# nbiot_gps.net
KiCad netlist of a schematic drawn in Altium Designer
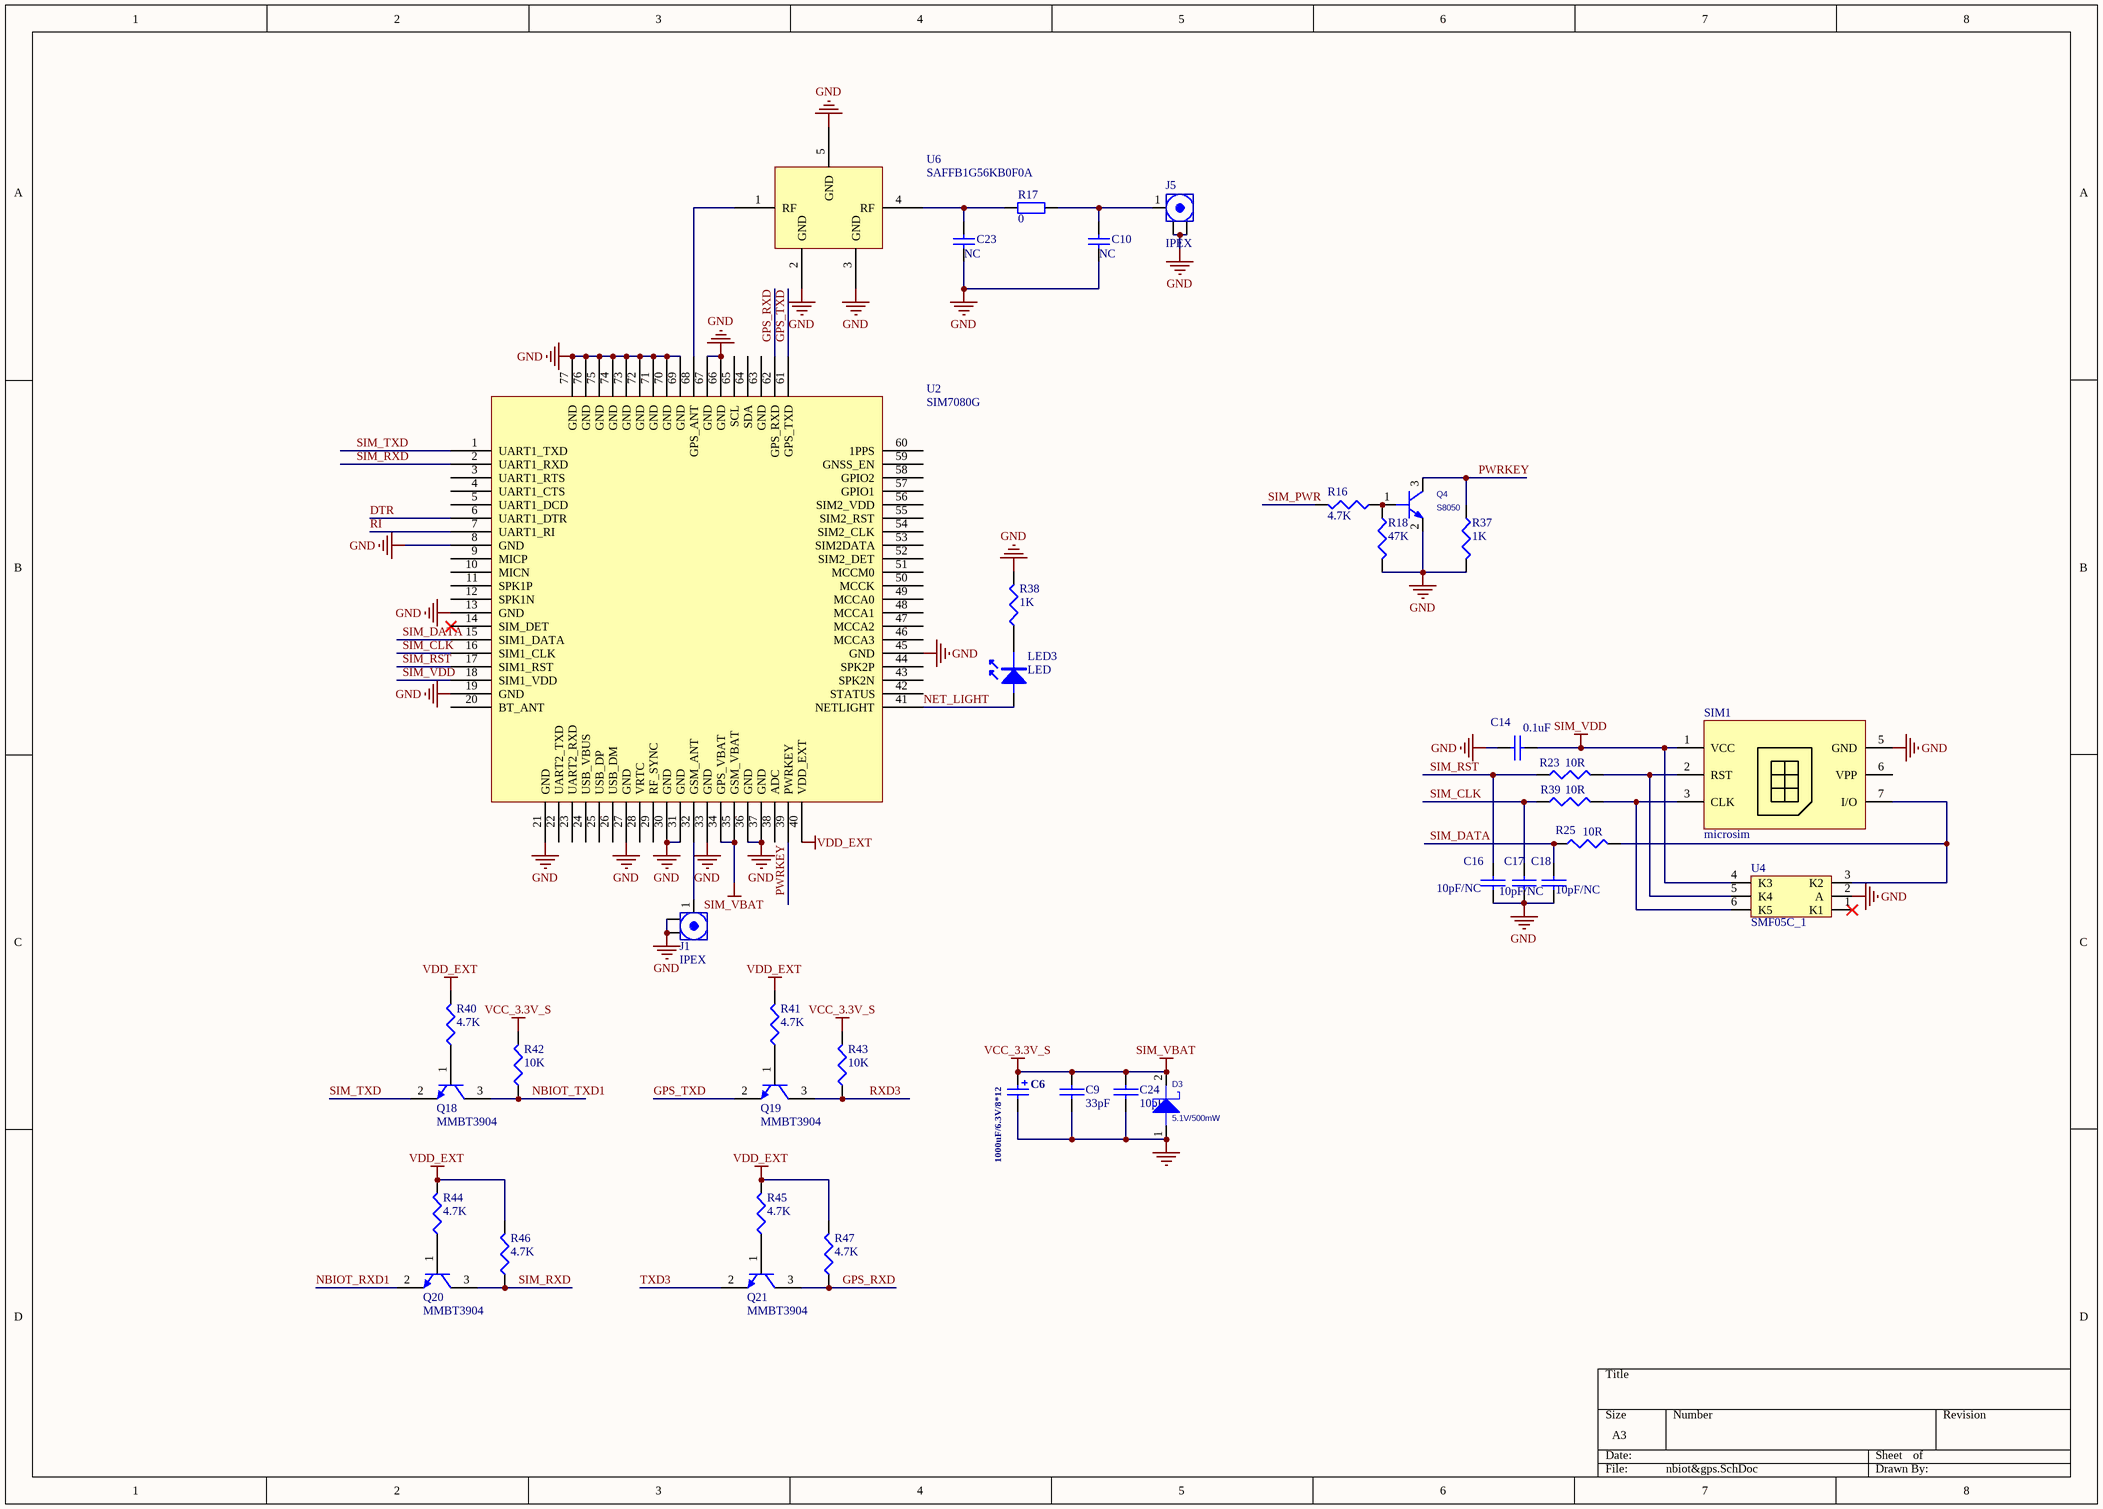
[diagram p0: nbiot&gps.SchDoc]

(export (version "E")
  (design (tool "Eeschema 10.0.6"))
  (components
    (comp (ref "C6")
      (value "1000uF/6.3V/8*12")
      (footprint "8*12")
      (description "Polarized Capacitor (Surface Mount)")
      (libsource (lib "KT_iBeacon") (part "Cap Pol3"))
    )
    (comp (ref "C9")
      (value "33pF")
      (footprint "0603C")
      (description "Capacitor")
      (libsource (lib "ZWLIntegrated_Library") (part "CAP"))
    )
    (comp (ref "C10")
      (value "NC")
      (footprint "0603C")
      (description "Capacitor")
      (fields (field (name "PUBLISHER") "Altium Limited"))
      (libsource (lib "Miscellaneous Devices") (part "Cap"))
    )
    (comp (ref "C14")
      (value "0.1uF")
      (footprint "0603C")
      (description "Capacitor")
      (libsource (lib "ZWLIntegrated_Library") (part "CAP"))
    )
    (comp (ref "C16")
      (value "10pF/NC")
      (footprint "0603C")
      (description "Capacitor")
      (libsource (lib "ZWLIntegrated_Library") (part "CAP"))
    )
    (comp (ref "C17")
      (value "10pF/NC")
      (footprint "0603C")
      (description "Capacitor")
      (libsource (lib "ZWLIntegrated_Library") (part "CAP"))
    )
    (comp (ref "C18")
      (value "10pF/NC")
      (footprint "0603C")
      (description "Capacitor")
      (libsource (lib "ZWLIntegrated_Library") (part "CAP"))
    )
    (comp (ref "C23")
      (value "NC")
      (footprint "0603C")
      (description "Capacitor")
      (fields (field (name "PUBLISHER") "Altium Limited"))
      (libsource (lib "Miscellaneous Devices") (part "Cap"))
    )
    (comp (ref "C24")
      (value "10pF")
      (footprint "0603C")
      (description "Capacitor")
      (libsource (lib "ZWLIntegrated_Library") (part "CAP"))
    )
    (comp (ref "D3")
      (value "5.1V/500mW")
      (footprint "LL-34(D1206)")
      (fields (field (name "Comment") "DIODE_SCHOTTKY_0"))
      (libsource (lib "KT_iBeacon") (part "DIODE_SCHOTTKY_0"))
    )
    (comp (ref "J1") (value "IPEX") (footprint "RF-UFL") (libsource (lib "我的元件库") (part "ANT")))
    (comp (ref "J5") (value "IPEX") (footprint "RF-UFL") (libsource (lib "我的元件库") (part "ANT")))
    (comp (ref "LED3") (value "LED") (footprint "0603LED") (libsource (lib "我的元件库") (part "LED")))
    (comp (ref "Q4") (value "S8050") (footprint "SOT23") (libsource (lib "*") (part "2N1069_1")))
    (comp (ref "Q18") (value "MMBT3904") (footprint "SOT23-3") (libsource (lib "Schlib1") (part "NPN")))
    (comp (ref "Q19") (value "MMBT3904") (footprint "SOT23-3") (libsource (lib "Schlib1") (part "NPN")))
    (comp (ref "Q20") (value "MMBT3904") (footprint "SOT23-3") (libsource (lib "Schlib1") (part "NPN")))
    (comp (ref "Q21") (value "MMBT3904") (footprint "SOT23-3") (libsource (lib "Schlib1") (part "NPN")))
    (comp (ref "R16")
      (value "4.7K")
      (footprint "0603R")
      (libsource (lib "ZWLIntegrated_Library") (part "RES1"))
    )
    (comp (ref "R17")
      (value "0")
      (footprint "0603R")
      (description "Resistor")
      (fields (field (name "PUBLISHER") "Altium Limited"))
      (libsource (lib "Miscellaneous Devices") (part "Res2"))
    )
    (comp (ref "R18")
      (value "47K")
      (footprint "0603R")
      (libsource (lib "ZWLIntegrated_Library") (part "RES1"))
    )
    (comp (ref "R23")
      (value "10R")
      (footprint "0603R")
      (libsource (lib "ZWLIntegrated_Library") (part "RES1"))
    )
    (comp (ref "R25")
      (value "10R")
      (footprint "0603R")
      (libsource (lib "ZWLIntegrated_Library") (part "RES1"))
    )
    (comp (ref "R37")
      (value "1K")
      (footprint "0603R")
      (libsource (lib "ZWLIntegrated_Library") (part "RES1"))
    )
    (comp (ref "R38")
      (value "1K")
      (footprint "0603R")
      (libsource (lib "ZWLIntegrated_Library") (part "RES1"))
    )
    (comp (ref "R39")
      (value "10R")
      (footprint "0603R")
      (libsource (lib "ZWLIntegrated_Library") (part "RES1"))
    )
    (comp (ref "R40")
      (value "4.7K")
      (footprint "0603R")
      (libsource (lib "ZWLIntegrated_Library") (part "RES1"))
    )
    (comp (ref "R41")
      (value "4.7K")
      (footprint "0603R")
      (libsource (lib "ZWLIntegrated_Library") (part "RES1"))
    )
    (comp (ref "R42")
      (value "10K")
      (footprint "0603R")
      (libsource (lib "ZWLIntegrated_Library") (part "RES1"))
    )
    (comp (ref "R43")
      (value "10K")
      (footprint "0603R")
      (libsource (lib "ZWLIntegrated_Library") (part "RES1"))
    )
    (comp (ref "R44")
      (value "4.7K")
      (footprint "0603R")
      (libsource (lib "ZWLIntegrated_Library") (part "RES1"))
    )
    (comp (ref "R45")
      (value "4.7K")
      (footprint "0603R")
      (libsource (lib "ZWLIntegrated_Library") (part "RES1"))
    )
    (comp (ref "R46")
      (value "4.7K")
      (footprint "0603R")
      (libsource (lib "ZWLIntegrated_Library") (part "RES1"))
    )
    (comp (ref "R47")
      (value "4.7K")
      (footprint "0603R")
      (libsource (lib "ZWLIntegrated_Library") (part "RES1"))
    )
    (comp (ref "SIM1")
      (value "microsim")
      (footprint "Nano SIM")
      (libsource (lib "SIM800C 原理图库") (part "microsim"))
    )
    (comp (ref "U2")
      (value "SIM7080G")
      (footprint "SIM868")
      (libsource (lib "stm32") (part "SIM868E/SIM868"))
    )
    (comp (ref "U4")
      (value "SMF05C_1")
      (footprint "SC70-6L")
      (description "TVS")
      (libsource (lib "SIM800C 原理图库") (part "SMF05C_1"))
    )
    (comp (ref "U6")
      (value "SAFFB1G56KB0F0A")
      (footprint "SAFFB1G56KB0F0A")
      (libsource (lib "stm32") (part "SAFFB1G56KBOFA"))
    )
  )
  (nets
    (net (code "1") (name "/DTR") (class "Default")
      (node (ref "U2") (pin "6") (pinfunction "UART1_DTR_6") (pintype "passive"))
    )
    (net (code "2") (name "/GPS_RXD") (class "Default")
      (node (ref "Q21") (pin "3") (pinfunction "C_3") (pintype "passive"))
      (node (ref "R47") (pin "1") (pinfunction "1_1") (pintype "passive"))
      (node (ref "U2") (pin "62") (pinfunction "GPS_RXD_62") (pintype "passive"))
    )
    (net (code "3") (name "/GPS_TXD") (class "Default")
      (node (ref "Q19") (pin "2") (pinfunction "E_2") (pintype "passive"))
      (node (ref "U2") (pin "61") (pinfunction "GPS_TXD_61") (pintype "passive"))
    )
    (net (code "4") (name "/NBIOT_RXD1") (class "Default")
      (node (ref "Q20") (pin "2") (pinfunction "E_2") (pintype "passive"))
    )
    (net (code "5") (name "/NBIOT_TXD1") (class "Default")
      (node (ref "Q18") (pin "3") (pinfunction "C_3") (pintype "passive"))
      (node (ref "R42") (pin "1") (pinfunction "1_1") (pintype "passive"))
    )
    (net (code "6") (name "/NET_LIGHT") (class "Default")
      (node (ref "LED3") (pin "1") (pinfunction "1_1") (pintype "passive"))
      (node (ref "U2") (pin "41") (pinfunction "NETLIGHT_41") (pintype "passive"))
    )
    (net (code "7") (name "/PWRKEY") (class "Default")
      (node (ref "Q4") (pin "3") (pinfunction "C_3") (pintype "passive"))
      (node (ref "R37") (pin "1") (pinfunction "1_1") (pintype "passive"))
      (node (ref "U2") (pin "39") (pinfunction "PWRKEY_39") (pintype "passive"))
    )
    (net (code "8") (name "/RI") (class "Default")
      (node (ref "U2") (pin "7") (pinfunction "UART1_RI_7") (pintype "passive"))
    )
    (net (code "9") (name "/RXD3") (class "Default")
      (node (ref "Q19") (pin "3") (pinfunction "C_3") (pintype "passive"))
      (node (ref "R43") (pin "1") (pinfunction "1_1") (pintype "passive"))
    )
    (net (code "10") (name "/SIM_CLK") (class "Default")
      (node (ref "C17") (pin "2") (pinfunction "2_2") (pintype "passive"))
      (node (ref "R39") (pin "1") (pinfunction "1_1") (pintype "passive"))
      (node (ref "U2") (pin "16") (pinfunction "SIM1_CLK_16") (pintype "passive"))
    )
    (net (code "11") (name "/SIM_DATA") (class "Default")
      (node (ref "C18") (pin "2") (pinfunction "2_2") (pintype "passive"))
      (node (ref "R25") (pin "1") (pinfunction "1_1") (pintype "passive"))
      (node (ref "U2") (pin "15") (pinfunction "SIM1_DATA_15") (pintype "passive"))
    )
    (net (code "12") (name "/SIM_PWR") (class "Default")
      (node (ref "R16") (pin "2") (pinfunction "2_2") (pintype "passive"))
    )
    (net (code "13") (name "/SIM_RST") (class "Default")
      (node (ref "C16") (pin "2") (pinfunction "2_2") (pintype "passive"))
      (node (ref "R23") (pin "1") (pinfunction "1_1") (pintype "passive"))
      (node (ref "U2") (pin "17") (pinfunction "SIM1_RST_17") (pintype "passive"))
    )
    (net (code "14") (name "/SIM_RXD") (class "Default")
      (node (ref "Q20") (pin "3") (pinfunction "C_3") (pintype "passive"))
      (node (ref "R46") (pin "1") (pinfunction "1_1") (pintype "passive"))
      (node (ref "U2") (pin "2") (pinfunction "UART1_RXD_2") (pintype "passive"))
    )
    (net (code "15") (name "/SIM_TXD") (class "Default")
      (node (ref "Q18") (pin "2") (pinfunction "E_2") (pintype "passive"))
      (node (ref "U2") (pin "1") (pinfunction "UART1_TXD_1") (pintype "passive"))
    )
    (net (code "16") (name "/TXD3") (class "Default")
      (node (ref "Q21") (pin "2") (pinfunction "E_2") (pintype "passive"))
    )
    (net (code "17") (name "GND") (class "Default")
      (node (ref "C10") (pin "2") (pinfunction "2_2") (pintype "passive"))
      (node (ref "C14") (pin "1") (pinfunction "1_1") (pintype "passive"))
      (node (ref "C16") (pin "1") (pinfunction "1_1") (pintype "passive"))
      (node (ref "C17") (pin "1") (pinfunction "1_1") (pintype "passive"))
      (node (ref "C18") (pin "1") (pinfunction "1_1") (pintype "passive"))
      (node (ref "C23") (pin "2") (pinfunction "2_2") (pintype "passive"))
      (node (ref "C24") (pin "1") (pinfunction "1_1") (pintype "passive"))
      (node (ref "C6") (pin "2") (pinfunction "2_2") (pintype "passive"))
      (node (ref "C9") (pin "1") (pinfunction "1_1") (pintype "passive"))
      (node (ref "D3") (pin "1") (pinfunction "1_1") (pintype "passive"))
      (node (ref "J1") (pin "2") (pinfunction "Y_2") (pintype "passive"))
      (node (ref "J5") (pin "2") (pinfunction "Y_2") (pintype "passive"))
      (node (ref "Q4") (pin "2") (pinfunction "E_2") (pintype "passive"))
      (node (ref "R18") (pin "2") (pinfunction "2_2") (pintype "passive"))
      (node (ref "R37") (pin "2") (pinfunction "2_2") (pintype "passive"))
      (node (ref "R38") (pin "2") (pinfunction "2_2") (pintype "passive"))
      (node (ref "SIM1") (pin "5") (pinfunction "GND_5") (pintype "passive"))
      (node (ref "U2") (pin "13") (pinfunction "GND_13") (pintype "passive"))
      (node (ref "U2") (pin "19") (pinfunction "GND_19") (pintype "passive"))
      (node (ref "U2") (pin "21") (pinfunction "GND_21") (pintype "passive"))
      (node (ref "U2") (pin "27") (pinfunction "GND_27") (pintype "passive"))
      (node (ref "U2") (pin "30") (pinfunction "GND_30") (pintype "passive"))
      (node (ref "U2") (pin "31") (pinfunction "GND_31") (pintype "passive"))
      (node (ref "U2") (pin "33") (pinfunction "GND_33") (pintype "passive"))
      (node (ref "U2") (pin "36") (pinfunction "GND_36") (pintype "passive"))
      (node (ref "U2") (pin "37") (pinfunction "GND_37") (pintype "passive"))
      (node (ref "U2") (pin "45") (pinfunction "GND_45") (pintype "passive"))
      (node (ref "U2") (pin "66") (pinfunction "GND_66") (pintype "passive"))
      (node (ref "U2") (pin "67") (pinfunction "GND_67") (pintype "passive"))
      (node (ref "U2") (pin "69") (pinfunction "GND_69") (pintype "passive"))
      (node (ref "U2") (pin "70") (pinfunction "GND_70") (pintype "passive"))
      (node (ref "U2") (pin "71") (pinfunction "GND_71") (pintype "passive"))
      (node (ref "U2") (pin "72") (pinfunction "GND_72") (pintype "passive"))
      (node (ref "U2") (pin "73") (pinfunction "GND_73") (pintype "passive"))
      (node (ref "U2") (pin "74") (pinfunction "GND_74") (pintype "passive"))
      (node (ref "U2") (pin "75") (pinfunction "GND_75") (pintype "passive"))
      (node (ref "U2") (pin "76") (pinfunction "GND_76") (pintype "passive"))
      (node (ref "U2") (pin "77") (pinfunction "GND_77") (pintype "passive"))
      (node (ref "U2") (pin "8") (pinfunction "GND_8") (pintype "passive"))
      (node (ref "U4") (pin "2") (pinfunction "A_2") (pintype "passive"))
      (node (ref "U6") (pin "2") (pinfunction "GND_2") (pintype "passive"))
      (node (ref "U6") (pin "3") (pinfunction "GND_3") (pintype "passive"))
      (node (ref "U6") (pin "5") (pinfunction "GND_5") (pintype "passive"))
    )
    (net (code "18") (name "Net-(C23-Pad1)") (class "Default")
      (node (ref "C23") (pin "1") (pinfunction "1_1") (pintype "passive"))
      (node (ref "R17") (pin "1") (pinfunction "1_1") (pintype "passive"))
      (node (ref "U6") (pin "4") (pinfunction "RF_4") (pintype "passive"))
    )
    (net (code "19") (name "Net-(J1-X)") (class "Default")
      (node (ref "J1") (pin "1") (pinfunction "X_1") (pintype "passive"))
      (node (ref "U2") (pin "32") (pinfunction "GSM_ANT_32") (pintype "passive"))
    )
    (net (code "20") (name "Net-(J5-X)") (class "Default")
      (node (ref "C10") (pin "1") (pinfunction "1_1") (pintype "passive"))
      (node (ref "J5") (pin "1") (pinfunction "X_1") (pintype "passive"))
      (node (ref "R17") (pin "2") (pinfunction "2_2") (pintype "passive"))
    )
    (net (code "21") (name "Net-(LED3-Pad2)") (class "Default")
      (node (ref "LED3") (pin "2") (pinfunction "2_2") (pintype "passive"))
      (node (ref "R38") (pin "1") (pinfunction "1_1") (pintype "passive"))
    )
    (net (code "22") (name "Net-(Q4-B)") (class "Default")
      (node (ref "Q4") (pin "1") (pinfunction "B_1") (pintype "passive"))
      (node (ref "R16") (pin "1") (pinfunction "1_1") (pintype "passive"))
      (node (ref "R18") (pin "1") (pinfunction "1_1") (pintype "passive"))
    )
    (net (code "23") (name "Net-(Q18-B)") (class "Default")
      (node (ref "Q18") (pin "1") (pinfunction "B_1") (pintype "passive"))
      (node (ref "R40") (pin "1") (pinfunction "1_1") (pintype "passive"))
    )
    (net (code "24") (name "Net-(Q19-B)") (class "Default")
      (node (ref "Q19") (pin "1") (pinfunction "B_1") (pintype "passive"))
      (node (ref "R41") (pin "1") (pinfunction "1_1") (pintype "passive"))
    )
    (net (code "25") (name "Net-(Q20-B)") (class "Default")
      (node (ref "Q20") (pin "1") (pinfunction "B_1") (pintype "passive"))
      (node (ref "R44") (pin "1") (pinfunction "1_1") (pintype "passive"))
    )
    (net (code "26") (name "Net-(Q21-B)") (class "Default")
      (node (ref "Q21") (pin "1") (pinfunction "B_1") (pintype "passive"))
      (node (ref "R45") (pin "1") (pinfunction "1_1") (pintype "passive"))
    )
    (net (code "27") (name "Net-(SIM1-CLK)") (class "Default")
      (node (ref "R39") (pin "2") (pinfunction "2_2") (pintype "passive"))
      (node (ref "SIM1") (pin "3") (pinfunction "CLK_3") (pintype "passive"))
      (node (ref "U4") (pin "6") (pinfunction "K5_6") (pintype "passive"))
    )
    (net (code "28") (name "Net-(SIM1-I{slash}O)") (class "Default")
      (node (ref "R25") (pin "2") (pinfunction "2_2") (pintype "passive"))
      (node (ref "SIM1") (pin "7") (pinfunction "I/O_7") (pintype "passive"))
      (node (ref "U4") (pin "3") (pinfunction "K2_3") (pintype "passive"))
    )
    (net (code "29") (name "Net-(SIM1-RST)") (class "Default")
      (node (ref "R23") (pin "2") (pinfunction "2_2") (pintype "passive"))
      (node (ref "SIM1") (pin "2") (pinfunction "RST_2") (pintype "passive"))
      (node (ref "U4") (pin "5") (pinfunction "K4_5") (pintype "passive"))
    )
    (net (code "30") (name "Net-(U2-GPS_ANT)") (class "Default")
      (node (ref "U2") (pin "68") (pinfunction "GPS_ANT_68") (pintype "passive"))
      (node (ref "U6") (pin "1") (pinfunction "RF_1") (pintype "passive"))
    )
    (net (code "31") (name "SIM_VBAT") (class "Default")
      (node (ref "C24") (pin "2") (pinfunction "2_2") (pintype "passive"))
      (node (ref "C6") (pin "1") (pinfunction "1_1") (pintype "passive"))
      (node (ref "C9") (pin "2") (pinfunction "2_2") (pintype "passive"))
      (node (ref "D3") (pin "2") (pinfunction "2_2") (pintype "passive"))
      (node (ref "R42") (pin "2") (pinfunction "2_2") (pintype "passive"))
      (node (ref "R43") (pin "2") (pinfunction "2_2") (pintype "passive"))
      (node (ref "U2") (pin "34") (pinfunction "GPS_VBAT_34") (pintype "passive"))
      (node (ref "U2") (pin "35") (pinfunction "GSM_VBAT_35") (pintype "passive"))
    )
    (net (code "32") (name "SIM_VDD") (class "Default")
      (node (ref "C14") (pin "2") (pinfunction "2_2") (pintype "passive"))
      (node (ref "SIM1") (pin "1") (pinfunction "VCC_1") (pintype "passive"))
      (node (ref "U2") (pin "18") (pinfunction "SIM1_VDD_18") (pintype "passive"))
      (node (ref "U4") (pin "4") (pinfunction "K3_4") (pintype "passive"))
    )
    (net (code "33") (name "VDD_EXT") (class "Default")
      (node (ref "R40") (pin "2") (pinfunction "2_2") (pintype "passive"))
      (node (ref "R41") (pin "2") (pinfunction "2_2") (pintype "passive"))
      (node (ref "R44") (pin "2") (pinfunction "2_2") (pintype "passive"))
      (node (ref "R45") (pin "2") (pinfunction "2_2") (pintype "passive"))
      (node (ref "R46") (pin "2") (pinfunction "2_2") (pintype "passive"))
      (node (ref "R47") (pin "2") (pinfunction "2_2") (pintype "passive"))
      (node (ref "U2") (pin "40") (pinfunction "VDD_EXT_40") (pintype "passive"))
    )
    (net (code "34") (name "unconnected-(SIM1-VPP-Pad6)") (class "Default")
      (node (ref "SIM1") (pin "6") (pinfunction "VPP_6") (pintype "passive"))
    )
    (net (code "35") (name "unconnected-(U2-1PPS-Pad60)") (class "Default")
      (node (ref "U2") (pin "60") (pinfunction "1PPS_60") (pintype "passive"))
    )
    (net (code "36") (name "unconnected-(U2-ADC-Pad38)") (class "Default")
      (node (ref "U2") (pin "38") (pinfunction "ADC_38") (pintype "passive"))
    )
    (net (code "37") (name "unconnected-(U2-BT_ANT-Pad20)") (class "Default")
      (node (ref "U2") (pin "20") (pinfunction "BT_ANT_20") (pintype "passive"))
    )
    (net (code "38") (name "unconnected-(U2-GND-Pad63)") (class "Default")
      (node (ref "U2") (pin "63") (pinfunction "GND_63") (pintype "passive"))
    )
    (net (code "39") (name "unconnected-(U2-GNSS_EN-Pad59)") (class "Default")
      (node (ref "U2") (pin "59") (pinfunction "GNSS_EN_59") (pintype "passive"))
    )
    (net (code "40") (name "unconnected-(U2-GPIO1-Pad57)") (class "Default")
      (node (ref "U2") (pin "57") (pinfunction "GPIO1_57") (pintype "passive"))
    )
    (net (code "41") (name "unconnected-(U2-GPIO2-Pad58)") (class "Default")
      (node (ref "U2") (pin "58") (pinfunction "GPIO2_58") (pintype "passive"))
    )
    (net (code "42") (name "unconnected-(U2-MCCA0-Pad49)") (class "Default")
      (node (ref "U2") (pin "49") (pinfunction "MCCA0_49") (pintype "passive"))
    )
    (net (code "43") (name "unconnected-(U2-MCCA1-Pad48)") (class "Default")
      (node (ref "U2") (pin "48") (pinfunction "MCCA1_48") (pintype "passive"))
    )
    (net (code "44") (name "unconnected-(U2-MCCA2-Pad47)") (class "Default")
      (node (ref "U2") (pin "47") (pinfunction "MCCA2_47") (pintype "passive"))
    )
    (net (code "45") (name "unconnected-(U2-MCCA3-Pad46)") (class "Default")
      (node (ref "U2") (pin "46") (pinfunction "MCCA3_46") (pintype "passive"))
    )
    (net (code "46") (name "unconnected-(U2-MCCK-Pad50)") (class "Default")
      (node (ref "U2") (pin "50") (pinfunction "MCCK_50") (pintype "passive"))
    )
    (net (code "47") (name "unconnected-(U2-MCCM0-Pad51)") (class "Default")
      (node (ref "U2") (pin "51") (pinfunction "MCCM0_51") (pintype "passive"))
    )
    (net (code "48") (name "unconnected-(U2-MICN-Pad10)") (class "Default")
      (node (ref "U2") (pin "10") (pinfunction "MICN_10") (pintype "passive"))
    )
    (net (code "49") (name "unconnected-(U2-MICP-Pad9)") (class "Default")
      (node (ref "U2") (pin "9") (pinfunction "MICP_9") (pintype "passive"))
    )
    (net (code "50") (name "unconnected-(U2-RF_SYNC-Pad29)") (class "Default")
      (node (ref "U2") (pin "29") (pinfunction "RF_SYNC_29") (pintype "passive"))
    )
    (net (code "51") (name "unconnected-(U2-SCL-Pad65)") (class "Default")
      (node (ref "U2") (pin "65") (pinfunction "SCL_65") (pintype "passive"))
    )
    (net (code "52") (name "unconnected-(U2-SDA-Pad64)") (class "Default")
      (node (ref "U2") (pin "64") (pinfunction "SDA_64") (pintype "passive"))
    )
    (net (code "53") (name "unconnected-(U2-SIM2DATA-Pad53)") (class "Default")
      (node (ref "U2") (pin "53") (pinfunction "SIM2DATA_53") (pintype "passive"))
    )
    (net (code "54") (name "unconnected-(U2-SIM2_CLK-Pad54)") (class "Default")
      (node (ref "U2") (pin "54") (pinfunction "SIM2_CLK_54") (pintype "passive"))
    )
    (net (code "55") (name "unconnected-(U2-SIM2_DET-Pad52)") (class "Default")
      (node (ref "U2") (pin "52") (pinfunction "SIM2_DET_52") (pintype "passive"))
    )
    (net (code "56") (name "unconnected-(U2-SIM2_RST-Pad55)") (class "Default")
      (node (ref "U2") (pin "55") (pinfunction "SIM2_RST_55") (pintype "passive"))
    )
    (net (code "57") (name "unconnected-(U2-SIM2_VDD-Pad56)") (class "Default")
      (node (ref "U2") (pin "56") (pinfunction "SIM2_VDD_56") (pintype "passive"))
    )
    (net (code "58") (name "unconnected-(U2-SIM_DET-Pad14)") (class "Default")
      (node (ref "U2") (pin "14") (pinfunction "SIM_DET_14") (pintype "passive+no_connect"))
    )
    (net (code "59") (name "unconnected-(U2-SPK1N-Pad12)") (class "Default")
      (node (ref "U2") (pin "12") (pinfunction "SPK1N_12") (pintype "passive"))
    )
    (net (code "60") (name "unconnected-(U2-SPK1P-Pad11)") (class "Default")
      (node (ref "U2") (pin "11") (pinfunction "SPK1P_11") (pintype "passive"))
    )
    (net (code "61") (name "unconnected-(U2-SPK2N-Pad43)") (class "Default")
      (node (ref "U2") (pin "43") (pinfunction "SPK2N_43") (pintype "passive"))
    )
    (net (code "62") (name "unconnected-(U2-SPK2P-Pad44)") (class "Default")
      (node (ref "U2") (pin "44") (pinfunction "SPK2P_44") (pintype "passive"))
    )
    (net (code "63") (name "unconnected-(U2-STATUS-Pad42)") (class "Default")
      (node (ref "U2") (pin "42") (pinfunction "STATUS_42") (pintype "passive"))
    )
    (net (code "64") (name "unconnected-(U2-UART1_CTS-Pad4)") (class "Default")
      (node (ref "U2") (pin "4") (pinfunction "UART1_CTS_4") (pintype "passive"))
    )
    (net (code "65") (name "unconnected-(U2-UART1_DCD-Pad5)") (class "Default")
      (node (ref "U2") (pin "5") (pinfunction "UART1_DCD_5") (pintype "passive"))
    )
    (net (code "66") (name "unconnected-(U2-UART1_RTS-Pad3)") (class "Default")
      (node (ref "U2") (pin "3") (pinfunction "UART1_RTS_3") (pintype "passive"))
    )
    (net (code "67") (name "unconnected-(U2-UART2_RXD-Pad23)") (class "Default")
      (node (ref "U2") (pin "23") (pinfunction "UART2_RXD_23") (pintype "passive"))
    )
    (net (code "68") (name "unconnected-(U2-UART2_TXD-Pad22)") (class "Default")
      (node (ref "U2") (pin "22") (pinfunction "UART2_TXD_22") (pintype "passive"))
    )
    (net (code "69") (name "unconnected-(U2-USB_DM-Pad26)") (class "Default")
      (node (ref "U2") (pin "26") (pinfunction "USB_DM_26") (pintype "passive"))
    )
    (net (code "70") (name "unconnected-(U2-USB_DP-Pad25)") (class "Default")
      (node (ref "U2") (pin "25") (pinfunction "USB_DP_25") (pintype "passive"))
    )
    (net (code "71") (name "unconnected-(U2-USB_VBUS-Pad24)") (class "Default")
      (node (ref "U2") (pin "24") (pinfunction "USB_VBUS_24") (pintype "passive"))
    )
    (net (code "72") (name "unconnected-(U2-VRTC-Pad28)") (class "Default")
      (node (ref "U2") (pin "28") (pinfunction "VRTC_28") (pintype "passive"))
    )
    (net (code "73") (name "unconnected-(U4-K1-Pad1)") (class "Default")
      (node (ref "U4") (pin "1") (pinfunction "K1_1") (pintype "passive+no_connect"))
    )
  )
)
